# Sheet1.net
KiCad netlist of a schematic drawn in Altium Designer
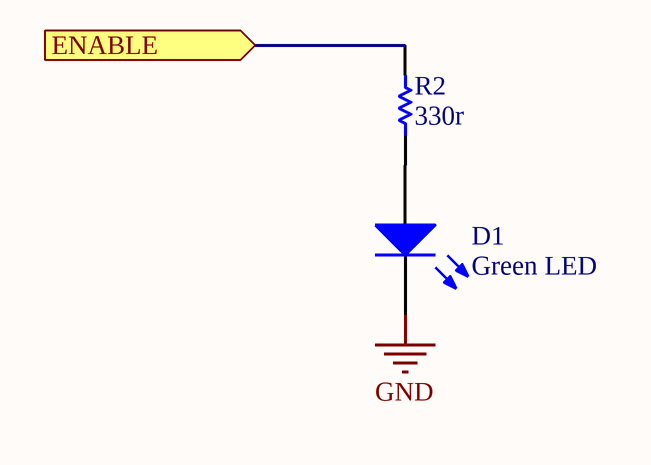
[diagram p0: Sheet1.SchDoc]

(export (version "E")
  (design (tool "Eeschema 10.0.6"))
  (components
    (comp (ref "D1")
      (value "Green LED")
      (footprint "LED-0")
      (description "Typical INFRARED GaAs LED")
      (fields (field (name "PUBLISHER") "Altium Limited"))
      (libsource (lib "Miscellaneous Devices") (part "LED0"))
    )
    (comp (ref "R2")
      (value "330r")
      (footprint "AXIAL-0.3")
      (description "Resistor")
      (fields (field (name "PUBLISHER") "Altium Limited"))
      (libsource (lib "Miscellaneous Devices") (part "Res1"))
    )
  )
  (nets
    (net (code "1") (name "/ENABLE") (class "Default")
      (node (ref "R2") (pin "2") (pinfunction "2_2") (pintype "passive"))
    )
    (net (code "2") (name "GND") (class "Default")
      (node (ref "D1") (pin "2") (pinfunction "K_2") (pintype "passive"))
    )
    (net (code "3") (name "Net-(D1-A)") (class "Default")
      (node (ref "D1") (pin "1") (pinfunction "A_1") (pintype "passive"))
      (node (ref "R2") (pin "1") (pinfunction "1_1") (pintype "passive"))
    )
  )
)
